# power-supply.net
KiCad netlist of a schematic drawn in Altium Designer
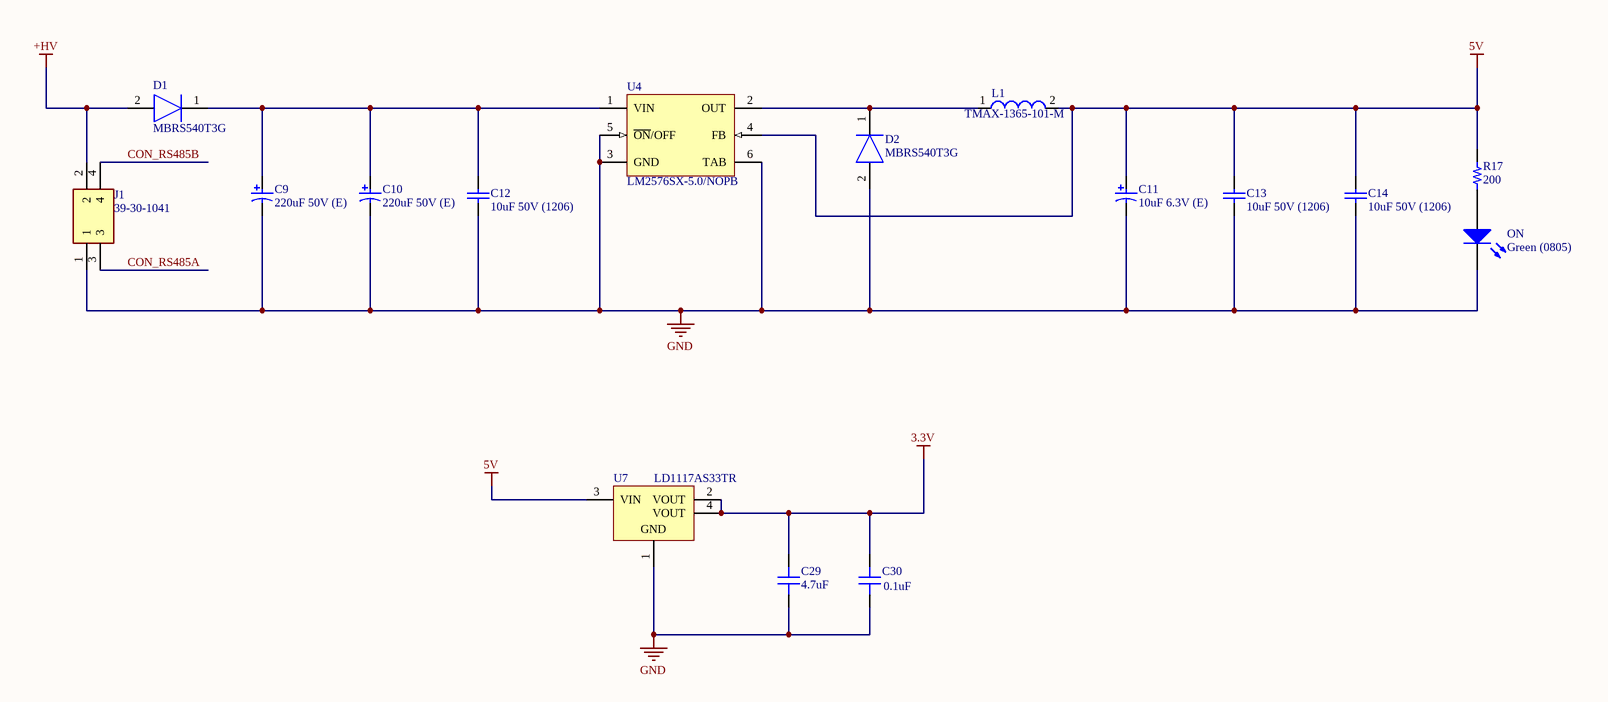
[diagram p0: power-supply.SchDoc]

(export (version "E")
  (design (tool "Eeschema 10.0.6"))
  (components
    (comp (ref "C9")
      (value "220uF 50V (E)")
      (footprint "PNSC-EEE-1HA221P_L")
      (fields (field (name "MANUFACTURER") "Panasonic"))
      (libsource (lib "Altium Content Vault") (part "CAP-P-2"))
    )
    (comp (ref "C10")
      (value "220uF 50V (E)")
      (footprint "PNSC-EEE-1HA221P_L")
      (fields (field (name "MANUFACTURER") "Panasonic"))
      (libsource (lib "Altium Content Vault") (part "CAP-P-2"))
    )
    (comp (ref "C11")
      (value "10uF 6.3V (E)")
      (footprint "NIC-CAPA2-8X10_V")
      (fields (field (name "MANUFACTURER") "Nichicon") (field (name "PARTNUMBER") "UUD0J102MNL1GS"))
      (libsource (lib "Altium Content Vault") (part "NIC-CAP-P-2"))
    )
    (comp (ref "C12")
      (value "10uF 50V (1206)")
      (footprint "CAPC3216X229X50LL20T25")
      (description "Chip Capacitor, 10 uF, +/- 10%, 25 V, -55 to 85 degC, 1206 (3216 Metric), RoHS, Tape and Reel")
      (fields (field (name "MANUFACTURER") "AVX"))
      (libsource (lib "Altium Content Vault") (part "CAP-NP-2"))
    )
    (comp (ref "C13")
      (value "10uF 50V (1206)")
      (footprint "CAPC3216X229X50LL20T25")
      (description "Chip Capacitor, 10 uF, +/- 10%, 25 V, -55 to 85 degC, 1206 (3216 Metric), RoHS, Tape and Reel")
      (fields (field (name "MANUFACTURER") "AVX"))
      (libsource (lib "Altium Content Vault") (part "CAP-NP-2"))
    )
    (comp (ref "C14")
      (value "10uF 50V (1206)")
      (footprint "CAPC3216X229X50LL20T25")
      (description "Chip Capacitor, 10 uF, +/- 10%, 25 V, -55 to 85 degC, 1206 (3216 Metric), RoHS, Tape and Reel")
      (fields (field (name "MANUFACTURER") "AVX"))
      (libsource (lib "Altium Content Vault") (part "CAP-NP-2"))
    )
    (comp (ref "C29")
      (value "4.7uF")
      (footprint "CAP 1206_3216 - 1.8MM")
      (description "CAP CERAMIC 16V X5R 1206")
      (fields (field (name "PART NUMBER") "C1206C335K4PACTU") (field (name "MANUFACTURER") "KEMET"))
      (libsource (lib "Celestial Altium Library - altium_library") (part "Capacitor"))
    )
    (comp (ref "C30")
      (value "0.1uF")
      (footprint "CAP 0603_1608")
      (description "CAP CERAMIC 50V X7R 0603")
      (fields
        (field (name "PART NUMBER") "VJ0603Y332JXACW1BC")
        (field (name "MANUFACTURER") "Vishay Vitramon")
      )
      (libsource (lib "Celestial Altium Library - altium_library") (part "Capacitor"))
    )
    (comp (ref "D1")
      (value "MBRS540T3G")
      (footprint "SamacSys:DIOM7958X256N")
      (description "Diode")
      (fields (field (name "MOUSER PART NUMBER") "863-MBRS540T3G") (field (name "RS PART NUMBER") "6880512"))
      (libsource (lib "*") (part "MBRS540T3G"))
    )
    (comp (ref "D2")
      (value "MBRS540T3G")
      (footprint "SamacSys:DIOM7958X256N")
      (description "Diode")
      (fields (field (name "MOUSER PART NUMBER") "863-MBRS540T3G") (field (name "RS PART NUMBER") "6880512"))
      (libsource (lib "*") (part "MBRS540T3G"))
    )
    (comp (ref "J1")
      (value "39-30-1041")
      (footprint "SamacSys:39-30-1040")
      (description "Connector")
      (fields (field (name "MOUSER PART NUMBER") "538-39-30-1041") (field (name "RS PART NUMBER") "6705754"))
      (libsource (lib "*") (part "39-30-1041"))
    )
    (comp (ref "L1")
      (value "TMAX-1365-101-M")
      (footprint "WE-HCI-1365")
      (description "SMD Flat Wire High Current Inductor WE-HCI, L=33.0 µH")
      (fields (field (name "MANUFACTURER") "Wuerth Elektronik") (field (name "PARTNUMBER") "7443551331"))
      (libsource (lib "Altium Content Vault") (part "PAS-IND-INDUCTOR-2"))
    )
    (comp (ref "ON")
      (value "Green (0805)")
      (footprint "0805_A")
      (description "SMD mono-color Chip LED, WL-SMCW, Green")
      (fields (field (name "PARTNUMBER") "150080GS75000") (field (name "MANUFACTURER") "Wuerth Elektronik"))
      (libsource (lib "Altium Content Vault") (part "WE-LED_K1A2-2"))
    )
    (comp (ref "R17")
      (value "200")
      (footprint "RES 0603_1608")
      (description "Resistor")
      (fields (field (name "PART NUMBER") "CRCW060329K4FKEA") (field (name "MANUFACTURER") "Vishay Dale"))
      (libsource (lib "Celestial Altium Library - altium_library") (part "Resistor"))
    )
    (comp (ref "U4")
      (value "LM2576SX-5.0/NOPB")
      (footprint "KTT0005B_M")
      (description "SIMPLE SWITCHER® 3A Step-Down Voltage Regulator, 5-pin TO-263, Pb-Free")
      (fields (field (name "MANUFACTURER") "Texas Instruments"))
      (libsource (lib "Altium Content Vault") (part "PM-REG-LM2575HVS-12"))
    )
    (comp (ref "U7")
      (value "LD1117AS33TR")
      (footprint "SOT-223_M")
      (description "1A, Low Drop Positive Voltage Regulator, 3.3V, 4-Pin SOT-223, Tape and Reel")
      (libsource (lib "Altium Content Vault") (part "PM-REG-LD1117-SOT4"))
    )
  )
  (nets
    (net (code "1") (name "+HV") (class "Default")
      (node (ref "D1") (pin "2") (pinfunction "A_2") (pintype "passive"))
      (node (ref "J1") (pin "2") (pinfunction "2_2") (pintype "passive"))
    )
    (net (code "2") (name "/CON_RS485A") (class "Default")
      (node (ref "J1") (pin "3") (pinfunction "3_3") (pintype "passive"))
    )
    (net (code "3") (name "/CON_RS485B") (class "Default")
      (node (ref "J1") (pin "4") (pinfunction "4_4") (pintype "passive"))
    )
    (net (code "4") (name "3.3V") (class "Default")
      (node (ref "C29") (pin "2") (pinfunction "2_2") (pintype "passive"))
      (node (ref "C30") (pin "2") (pinfunction "2_2") (pintype "passive"))
      (node (ref "U7") (pin "2") (pinfunction "VOUT_2") (pintype "power_in"))
      (node (ref "U7") (pin "4") (pinfunction "VOUT_4") (pintype "power_in"))
    )
    (net (code "5") (name "5V") (class "Default")
      (node (ref "C11") (pin "1") (pinfunction "1_1") (pintype "passive"))
      (node (ref "C13") (pin "2") (pinfunction "2_2") (pintype "passive"))
      (node (ref "C14") (pin "2") (pinfunction "2_2") (pintype "passive"))
      (node (ref "L1") (pin "2") (pinfunction "2_2") (pintype "passive"))
      (node (ref "R17") (pin "2") (pinfunction "2_2") (pintype "passive"))
      (node (ref "U4") (pin "4") (pinfunction "FB_4") (pintype "input"))
      (node (ref "U7") (pin "3") (pinfunction "VIN_3") (pintype "power_in"))
    )
    (net (code "6") (name "GND") (class "Default")
      (node (ref "C10") (pin "2") (pinfunction "2_2") (pintype "passive"))
      (node (ref "C11") (pin "2") (pinfunction "2_2") (pintype "passive"))
      (node (ref "C12") (pin "1") (pinfunction "1_1") (pintype "passive"))
      (node (ref "C13") (pin "1") (pinfunction "1_1") (pintype "passive"))
      (node (ref "C14") (pin "1") (pinfunction "1_1") (pintype "passive"))
      (node (ref "C29") (pin "1") (pinfunction "1_1") (pintype "passive"))
      (node (ref "C30") (pin "1") (pinfunction "1_1") (pintype "passive"))
      (node (ref "C9") (pin "2") (pinfunction "2_2") (pintype "passive"))
      (node (ref "D2") (pin "2") (pinfunction "A_2") (pintype "passive"))
      (node (ref "J1") (pin "1") (pinfunction "1_1") (pintype "passive"))
      (node (ref "ON") (pin "1") (pinfunction "K_1") (pintype "passive"))
      (node (ref "U4") (pin "3") (pinfunction "GND_3") (pintype "power_in"))
      (node (ref "U4") (pin "5") (pinfunction "~{ON}/OFF_5") (pintype "input"))
      (node (ref "U4") (pin "6") (pinfunction "TAB_6") (pintype "power_in"))
      (node (ref "U7") (pin "1") (pinfunction "GND_1") (pintype "power_in"))
    )
    (net (code "7") (name "Net-(D1-K)") (class "Default")
      (node (ref "C10") (pin "1") (pinfunction "1_1") (pintype "passive"))
      (node (ref "C12") (pin "2") (pinfunction "2_2") (pintype "passive"))
      (node (ref "C9") (pin "1") (pinfunction "1_1") (pintype "passive"))
      (node (ref "D1") (pin "1") (pinfunction "K_1") (pintype "passive"))
      (node (ref "U4") (pin "1") (pinfunction "VIN_1") (pintype "power_in"))
    )
    (net (code "8") (name "Net-(D2-K)") (class "Default")
      (node (ref "D2") (pin "1") (pinfunction "K_1") (pintype "passive"))
      (node (ref "L1") (pin "1") (pinfunction "1_1") (pintype "passive"))
      (node (ref "U4") (pin "2") (pinfunction "OUT_2") (pintype "power_in"))
    )
    (net (code "9") (name "Net-(ON-A)") (class "Default")
      (node (ref "ON") (pin "2") (pinfunction "A_2") (pintype "passive"))
      (node (ref "R17") (pin "1") (pinfunction "1_1") (pintype "passive"))
    )
  )
)
